# Atishay_EtchASketch.net
KiCad netlist of a schematic drawn in EAGLE
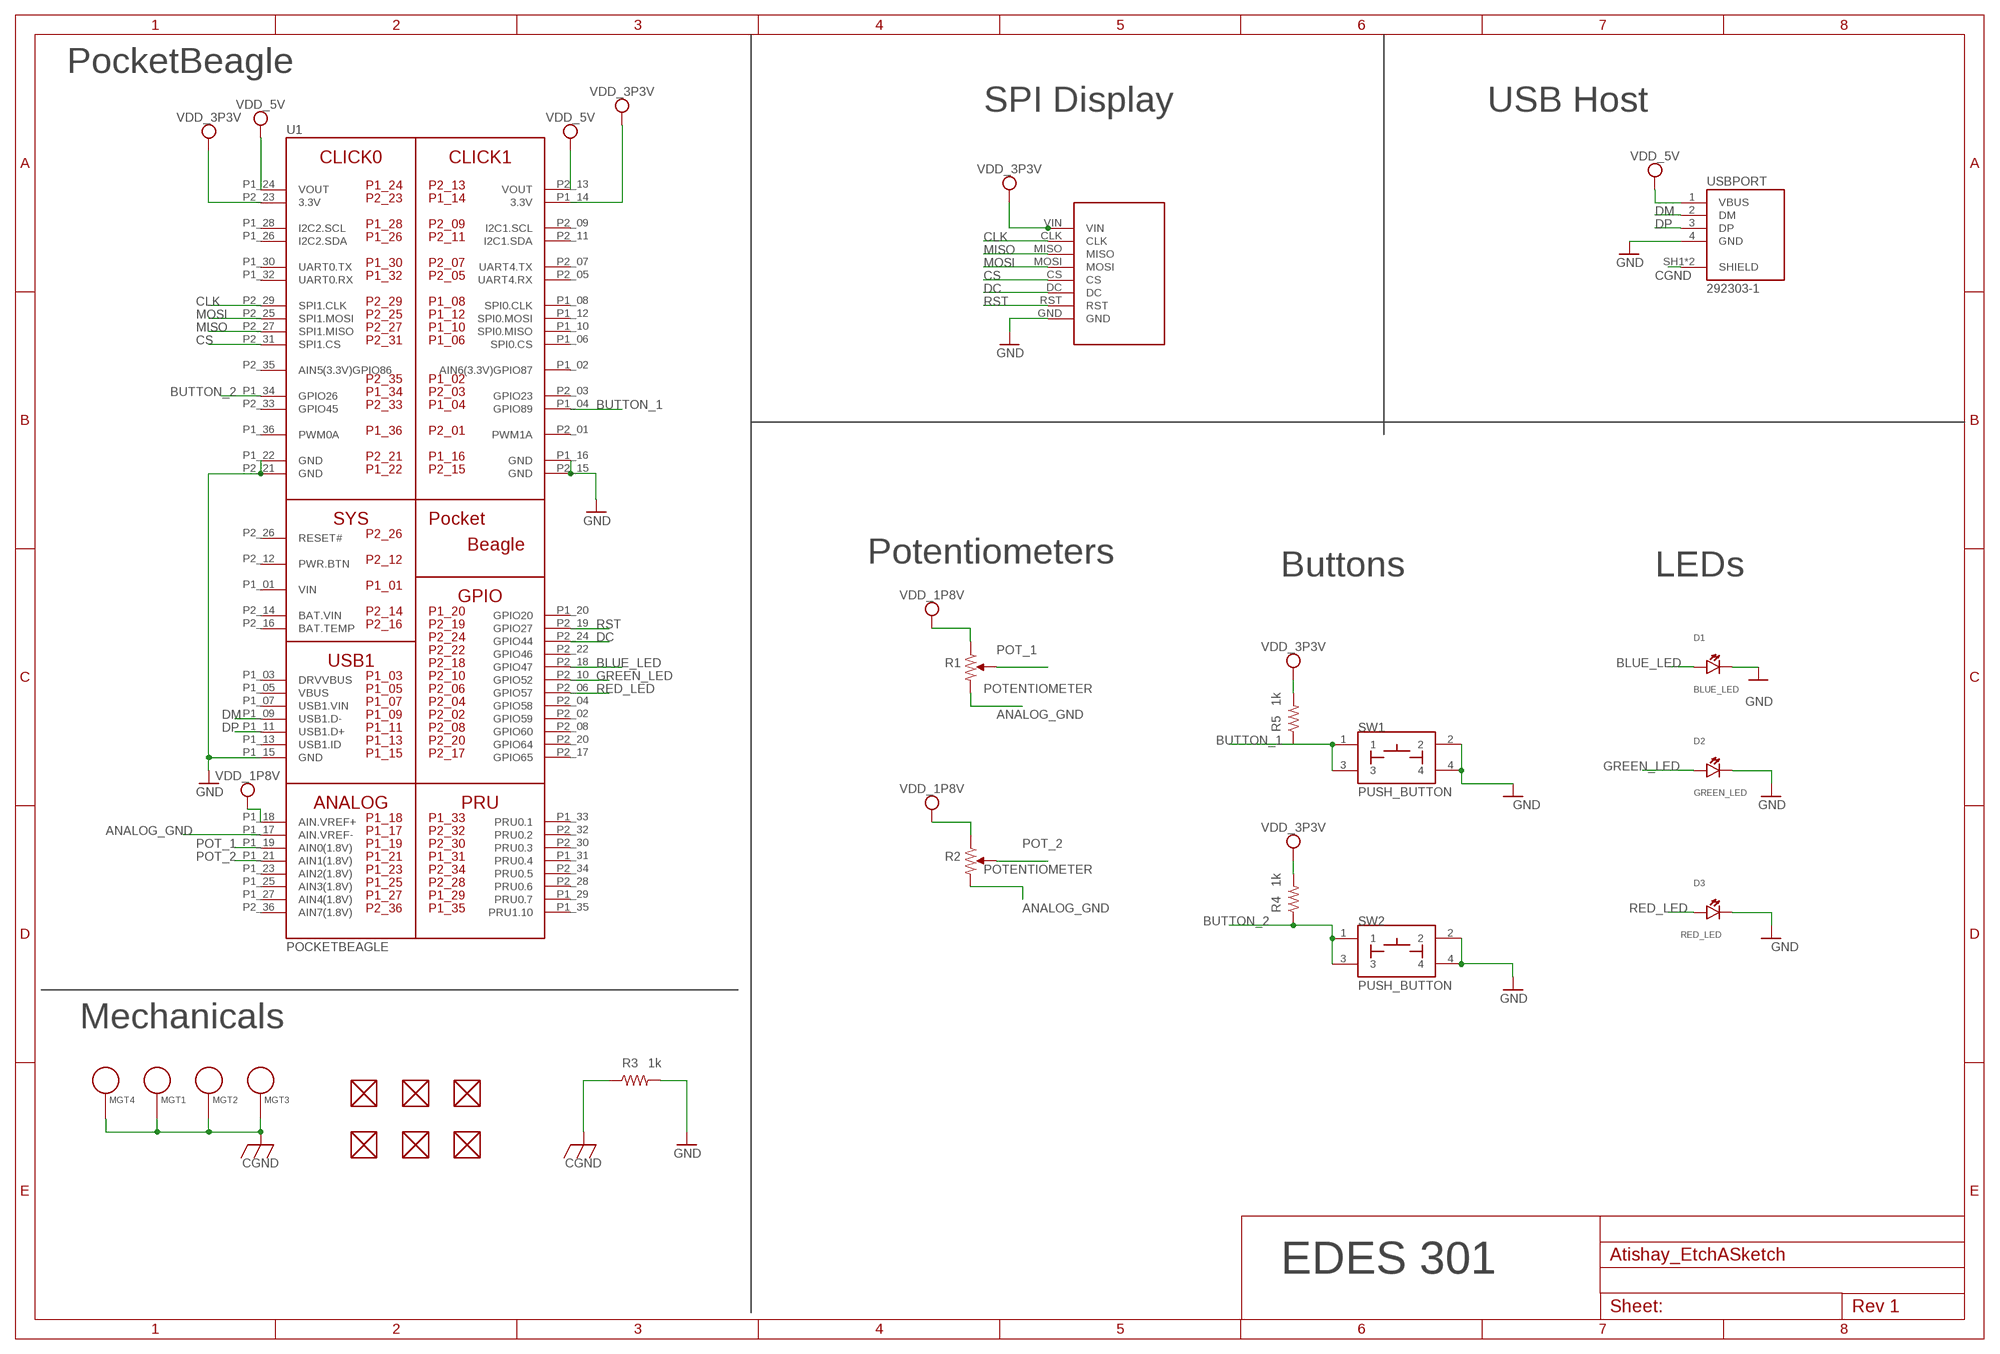
[diagram p0: schematic, sheet 1]

(export (version "E")
  (design (tool "Eeschema 10.0.6"))
  (components
    (comp (ref "D1")
      (value "BLUE_LED")
      (footprint "eagle-import:EIA-STD")
      (libsource (lib "eagle-import") (part "LED"))
    )
    (comp (ref "D2")
      (value "GREEN_LED")
      (footprint "eagle-import:EIA-STD")
      (libsource (lib "eagle-import") (part "LED"))
    )
    (comp (ref "D3")
      (value "RED_LED")
      (footprint "eagle-import:EIA-STD")
      (libsource (lib "eagle-import") (part "LED"))
    )
    (comp (ref "FUD1")
      (value "FIDUCIAL")
      (footprint "eagle-import:FIDUCIAL_40MIL")
      (libsource (lib "eagle-import") (part "FIDUCIAL"))
    )
    (comp (ref "FUD2")
      (value "FIDUCIAL")
      (footprint "eagle-import:FIDUCIAL_40MIL")
      (libsource (lib "eagle-import") (part "FIDUCIAL"))
    )
    (comp (ref "FUD3")
      (value "FIDUCIAL")
      (footprint "eagle-import:FIDUCIAL_40MIL")
      (libsource (lib "eagle-import") (part "FIDUCIAL"))
    )
    (comp (ref "FUD4")
      (value "FIDUCIAL")
      (footprint "eagle-import:FIDUCIAL_40MIL")
      (libsource (lib "eagle-import") (part "FIDUCIAL"))
    )
    (comp (ref "FUD5")
      (value "FIDUCIAL")
      (footprint "eagle-import:FIDUCIAL_40MIL")
      (libsource (lib "eagle-import") (part "FIDUCIAL"))
    )
    (comp (ref "FUD6")
      (value "FIDUCIAL")
      (footprint "eagle-import:FIDUCIAL_40MIL")
      (libsource (lib "eagle-import") (part "FIDUCIAL"))
    )
    (comp (ref "MGT1")
      (value "MOUNTING_HOLE")
      (footprint "eagle-import:MOUNTING_HOLE")
      (libsource (lib "eagle-import") (part "MOUNTING_HOLE"))
    )
    (comp (ref "MGT2")
      (value "MOUNTING_HOLE")
      (footprint "eagle-import:MOUNTING_HOLE")
      (libsource (lib "eagle-import") (part "MOUNTING_HOLE"))
    )
    (comp (ref "MGT3")
      (value "MOUNTING_HOLE")
      (footprint "eagle-import:MOUNTING_HOLE")
      (libsource (lib "eagle-import") (part "MOUNTING_HOLE"))
    )
    (comp (ref "MGT4")
      (value "MOUNTING_HOLE")
      (footprint "eagle-import:MOUNTING_HOLE")
      (libsource (lib "eagle-import") (part "MOUNTING_HOLE"))
    )
    (comp (ref "R1")
      (value "POTENTIOMETER")
      (footprint "eagle-import:POT-PO90S")
      (libsource (lib "eagle-import") (part "POTENTIOMETER"))
    )
    (comp (ref "R2")
      (value "POTENTIOMETER")
      (footprint "eagle-import:POT-PO90S")
      (libsource (lib "eagle-import") (part "POTENTIOMETER"))
    )
    (comp (ref "R3")
      (value "1k")
      (footprint "eagle-import:R0603")
      (libsource (lib "eagle-import") (part "R_R0603"))
    )
    (comp (ref "R4")
      (value "1k")
      (footprint "eagle-import:R0603")
      (libsource (lib "eagle-import") (part "R_R0603"))
    )
    (comp (ref "R5")
      (value "1k")
      (footprint "eagle-import:R0603")
      (libsource (lib "eagle-import") (part "R_R0603"))
    )
    (comp (ref "SPIDISPLAY")
      (value "SCREEN")
      (footprint "eagle-import:SCREEN")
      (libsource (lib "eagle-import") (part "SCREEN"))
    )
    (comp (ref "SW1")
      (value "PUSH_BUTTON")
      (footprint "eagle-import:BUTTON_12.5MM")
      (libsource (lib "eagle-import") (part "PUSH_BUTTON"))
    )
    (comp (ref "SW2")
      (value "PUSH_BUTTON")
      (footprint "eagle-import:BUTTON_12.5MM")
      (libsource (lib "eagle-import") (part "PUSH_BUTTON"))
    )
    (comp (ref "U1")
      (value "POCKETBEAGLE")
      (footprint "eagle-import:POCKETBEAGLE")
      (libsource (lib "eagle-import") (part "POCKETBEAGLE"))
    )
    (comp (ref "USBPORT")
      (value "292303-1")
      (footprint "eagle-import:TE_292303-1")
      (fields (field (name "MF") "TE Connectivity"))
      (libsource (lib "eagle-import") (part "292303-1"))
    )
  )
  (nets
    (net (code "1") (name "/ANALOG_GND") (class "Default")
      (node (ref "R1") (pin "CW") (pinfunction "CW_CW") (pintype "passive"))
      (node (ref "R2") (pin "CW") (pinfunction "CW_CW") (pintype "passive"))
      (node (ref "U1") (pin "P1_17") (pinfunction "AIN.VREF-_P1_17") (pintype "input"))
    )
    (net (code "2") (name "/BAT.VIN") (class "Default")
      (node (ref "U1") (pin "P2_14") (pinfunction "BAT.VIN_P2_14") (pintype "power_in"))
    )
    (net (code "3") (name "/BLUE_LED") (class "Default")
      (node (ref "D1") (pin "ANODE") (pinfunction "ANODE_ANODE") (pintype "bidirectional"))
      (node (ref "U1") (pin "P2_18") (pinfunction "GPIO47_P2_18") (pintype "bidirectional"))
    )
    (net (code "4") (name "/BUTTON_1") (class "Default")
      (node (ref "R5") (pin "1") (pinfunction "1_1") (pintype "passive"))
      (node (ref "SW1") (pin "1") (pinfunction "1_1") (pintype "bidirectional"))
      (node (ref "SW1") (pin "3") (pinfunction "3_3") (pintype "bidirectional"))
      (node (ref "U1") (pin "P1_04") (pinfunction "GPIO89_P1_04") (pintype "bidirectional"))
    )
    (net (code "5") (name "/BUTTON_2") (class "Default")
      (node (ref "R4") (pin "1") (pinfunction "1_1") (pintype "passive"))
      (node (ref "SW2") (pin "1") (pinfunction "1_1") (pintype "bidirectional"))
      (node (ref "SW2") (pin "3") (pinfunction "3_3") (pintype "bidirectional"))
      (node (ref "U1") (pin "P1_34") (pinfunction "GPIO26_P1_34") (pintype "bidirectional"))
    )
    (net (code "6") (name "/CLK") (class "Default")
      (node (ref "SPIDISPLAY") (pin "CLK") (pinfunction "CLK_CLK") (pintype "bidirectional"))
      (node (ref "U1") (pin "P2_29") (pinfunction "SPI1.CLK_P2_29") (pintype "bidirectional"))
    )
    (net (code "7") (name "/CS") (class "Default")
      (node (ref "SPIDISPLAY") (pin "CS") (pinfunction "CS_CS") (pintype "bidirectional"))
      (node (ref "U1") (pin "P2_31") (pinfunction "SPI1.CS_P2_31") (pintype "bidirectional"))
    )
    (net (code "8") (name "/DC") (class "Default")
      (node (ref "SPIDISPLAY") (pin "DC") (pinfunction "DC_DC") (pintype "bidirectional"))
      (node (ref "U1") (pin "P2_24") (pinfunction "GPIO44_P2_24") (pintype "bidirectional"))
    )
    (net (code "9") (name "/DM") (class "Default")
      (node (ref "U1") (pin "P1_09") (pinfunction "USB1.D-_P1_09") (pintype "bidirectional"))
      (node (ref "USBPORT") (pin "2") (pinfunction "DM_2") (pintype "passive"))
    )
    (net (code "10") (name "/DP") (class "Default")
      (node (ref "U1") (pin "P1_11") (pinfunction "USB1.D+_P1_11") (pintype "bidirectional"))
      (node (ref "USBPORT") (pin "3") (pinfunction "DP_3") (pintype "passive"))
    )
    (net (code "11") (name "/GREEN_LED") (class "Default")
      (node (ref "D2") (pin "ANODE") (pinfunction "ANODE_ANODE") (pintype "bidirectional"))
      (node (ref "U1") (pin "P2_10") (pinfunction "GPIO52_P2_10") (pintype "bidirectional"))
    )
    (net (code "12") (name "/MISO") (class "Default")
      (node (ref "SPIDISPLAY") (pin "MISO") (pinfunction "MISO_MISO") (pintype "bidirectional"))
      (node (ref "U1") (pin "P2_27") (pinfunction "SPI1.MISO_P2_27") (pintype "bidirectional"))
    )
    (net (code "13") (name "/MOSI") (class "Default")
      (node (ref "SPIDISPLAY") (pin "MOSI") (pinfunction "MOSI_MOSI") (pintype "bidirectional"))
      (node (ref "U1") (pin "P2_25") (pinfunction "SPI1.MOSI_P2_25") (pintype "bidirectional"))
    )
    (net (code "14") (name "/POT_1") (class "Default")
      (node (ref "R1") (pin "S") (pinfunction "S_S") (pintype "bidirectional"))
      (node (ref "U1") (pin "P1_19") (pinfunction "AIN0(1.8V)_P1_19") (pintype "input"))
    )
    (net (code "15") (name "/POT_2") (class "Default")
      (node (ref "R2") (pin "S") (pinfunction "S_S") (pintype "bidirectional"))
      (node (ref "U1") (pin "P1_21") (pinfunction "AIN1(1.8V)_P1_21") (pintype "input"))
    )
    (net (code "16") (name "/RED_LED") (class "Default")
      (node (ref "D3") (pin "ANODE") (pinfunction "ANODE_ANODE") (pintype "bidirectional"))
      (node (ref "U1") (pin "P2_06") (pinfunction "GPIO57_P2_06") (pintype "bidirectional"))
    )
    (net (code "17") (name "/RST") (class "Default")
      (node (ref "SPIDISPLAY") (pin "RST") (pinfunction "RST_RST") (pintype "bidirectional"))
      (node (ref "U1") (pin "P2_19") (pinfunction "GPIO27_P2_19") (pintype "bidirectional"))
    )
    (net (code "18") (name "/VIN") (class "Default")
      (node (ref "U1") (pin "P1_01") (pinfunction "VIN_P1_01") (pintype "power_in"))
    )
    (net (code "19") (name "CGND") (class "Default")
      (node (ref "MGT1") (pin "P$1") (pinfunction "P$1_P$1") (pintype "bidirectional"))
      (node (ref "MGT2") (pin "P$1") (pinfunction "P$1_P$1") (pintype "bidirectional"))
      (node (ref "MGT3") (pin "P$1") (pinfunction "P$1_P$1") (pintype "bidirectional"))
      (node (ref "MGT4") (pin "P$1") (pinfunction "P$1_P$1") (pintype "bidirectional"))
      (node (ref "R3") (pin "1") (pinfunction "1_1") (pintype "passive"))
      (node (ref "USBPORT") (pin "SH1") (pinfunction "SHIELD_SH1") (pintype "passive"))
      (node (ref "USBPORT") (pin "SH2") (pinfunction "SHIELD_SH2") (pintype "passive"))
    )
    (net (code "20") (name "GND") (class "Default")
      (node (ref "D1") (pin "CATHODE") (pinfunction "CATHODE_CATHODE") (pintype "bidirectional"))
      (node (ref "D2") (pin "CATHODE") (pinfunction "CATHODE_CATHODE") (pintype "bidirectional"))
      (node (ref "D3") (pin "CATHODE") (pinfunction "CATHODE_CATHODE") (pintype "bidirectional"))
      (node (ref "R3") (pin "2") (pinfunction "2_2") (pintype "passive"))
      (node (ref "SPIDISPLAY") (pin "GND") (pinfunction "GND_GND") (pintype "bidirectional"))
      (node (ref "SW1") (pin "2") (pinfunction "2_2") (pintype "bidirectional"))
      (node (ref "SW1") (pin "4") (pinfunction "4_4") (pintype "bidirectional"))
      (node (ref "SW2") (pin "2") (pinfunction "2_2") (pintype "bidirectional"))
      (node (ref "SW2") (pin "4") (pinfunction "4_4") (pintype "bidirectional"))
      (node (ref "U1") (pin "P1_15") (pinfunction "GND_P1_15") (pintype "bidirectional"))
      (node (ref "U1") (pin "P1_16") (pinfunction "GND_P1_16") (pintype "power_in"))
      (node (ref "U1") (pin "P1_22") (pinfunction "GND_P1_22") (pintype "power_in"))
      (node (ref "U1") (pin "P2_15") (pinfunction "GND_P2_15") (pintype "power_in"))
      (node (ref "U1") (pin "P2_21") (pinfunction "GND_P2_21") (pintype "power_in"))
      (node (ref "USBPORT") (pin "4") (pinfunction "GND_4") (pintype "passive"))
    )
    (net (code "21") (name "VDD_1P8V") (class "Default")
      (node (ref "R1") (pin "CCW") (pinfunction "CCW_CCW") (pintype "passive"))
      (node (ref "R2") (pin "CCW") (pinfunction "CCW_CCW") (pintype "passive"))
      (node (ref "U1") (pin "P1_18") (pinfunction "AIN.VREF+_P1_18") (pintype "input"))
    )
    (net (code "22") (name "VDD_3P3V") (class "Default")
      (node (ref "R4") (pin "2") (pinfunction "2_2") (pintype "passive"))
      (node (ref "R5") (pin "2") (pinfunction "2_2") (pintype "passive"))
      (node (ref "SPIDISPLAY") (pin "VIN") (pinfunction "VIN_VIN") (pintype "bidirectional"))
      (node (ref "U1") (pin "P1_14") (pinfunction "3.3V_P1_14") (pintype "power_in"))
      (node (ref "U1") (pin "P2_23") (pinfunction "3.3V_P2_23") (pintype "power_in"))
    )
    (net (code "23") (name "VDD_5V") (class "Default")
      (node (ref "U1") (pin "P1_24") (pinfunction "VOUT_P1_24") (pintype "power_in"))
      (node (ref "U1") (pin "P2_13") (pinfunction "VOUT_P2_13") (pintype "power_in"))
      (node (ref "USBPORT") (pin "1") (pinfunction "VBUS_1") (pintype "passive"))
    )
    (net (code "24") (name "unconnected-(FUD1-PadP$1)") (class "Default")
      (node (ref "FUD1") (pin "P$1") (pinfunction "P$1_P$1") (pintype "no_connect"))
    )
    (net (code "25") (name "unconnected-(FUD2-PadP$1)") (class "Default")
      (node (ref "FUD2") (pin "P$1") (pinfunction "P$1_P$1") (pintype "no_connect"))
    )
    (net (code "26") (name "unconnected-(FUD3-PadP$1)") (class "Default")
      (node (ref "FUD3") (pin "P$1") (pinfunction "P$1_P$1") (pintype "no_connect"))
    )
    (net (code "27") (name "unconnected-(FUD4-PadP$1)") (class "Default")
      (node (ref "FUD4") (pin "P$1") (pinfunction "P$1_P$1") (pintype "no_connect"))
    )
    (net (code "28") (name "unconnected-(FUD5-PadP$1)") (class "Default")
      (node (ref "FUD5") (pin "P$1") (pinfunction "P$1_P$1") (pintype "no_connect"))
    )
    (net (code "29") (name "unconnected-(FUD6-PadP$1)") (class "Default")
      (node (ref "FUD6") (pin "P$1") (pinfunction "P$1_P$1") (pintype "no_connect"))
    )
    (net (code "30") (name "unconnected-(U1-AIN2(1.8V)-PadP1_23)") (class "Default")
      (node (ref "U1") (pin "P1_23") (pinfunction "AIN2(1.8V)_P1_23") (pintype "input"))
    )
    (net (code "31") (name "unconnected-(U1-AIN3(1.8V)-PadP1_25)") (class "Default")
      (node (ref "U1") (pin "P1_25") (pinfunction "AIN3(1.8V)_P1_25") (pintype "input"))
    )
    (net (code "32") (name "unconnected-(U1-AIN4(1.8V)-PadP1_27)") (class "Default")
      (node (ref "U1") (pin "P1_27") (pinfunction "AIN4(1.8V)_P1_27") (pintype "input"))
    )
    (net (code "33") (name "unconnected-(U1-AIN5(3.3V)GPIO86-PadP2_35)") (class "Default")
      (node (ref "U1") (pin "P2_35") (pinfunction "AIN5(3.3V)GPIO86_P2_35") (pintype "bidirectional"))
    )
    (net (code "34") (name "unconnected-(U1-AIN6(3.3V)GPIO87-PadP1_02)") (class "Default")
      (node (ref "U1") (pin "P1_02") (pinfunction "AIN6(3.3V)GPIO87_P1_02") (pintype "bidirectional"))
    )
    (net (code "35") (name "unconnected-(U1-AIN7(1.8V)-PadP2_36)") (class "Default")
      (node (ref "U1") (pin "P2_36") (pinfunction "AIN7(1.8V)_P2_36") (pintype "input"))
    )
    (net (code "36") (name "unconnected-(U1-BAT.TEMP-PadP2_16)") (class "Default")
      (node (ref "U1") (pin "P2_16") (pinfunction "BAT.TEMP_P2_16") (pintype "input"))
    )
    (net (code "37") (name "unconnected-(U1-DRVVBUS-PadP1_03)") (class "Default")
      (node (ref "U1") (pin "P1_03") (pinfunction "DRVVBUS_P1_03") (pintype "bidirectional"))
    )
    (net (code "38") (name "unconnected-(U1-GPIO20-PadP1_20)") (class "Default")
      (node (ref "U1") (pin "P1_20") (pinfunction "GPIO20_P1_20") (pintype "bidirectional"))
    )
    (net (code "39") (name "unconnected-(U1-GPIO23-PadP2_03)") (class "Default")
      (node (ref "U1") (pin "P2_03") (pinfunction "GPIO23_P2_03") (pintype "bidirectional"))
    )
    (net (code "40") (name "unconnected-(U1-GPIO45-PadP2_33)") (class "Default")
      (node (ref "U1") (pin "P2_33") (pinfunction "GPIO45_P2_33") (pintype "bidirectional"))
    )
    (net (code "41") (name "unconnected-(U1-GPIO46-PadP2_22)") (class "Default")
      (node (ref "U1") (pin "P2_22") (pinfunction "GPIO46_P2_22") (pintype "bidirectional"))
    )
    (net (code "42") (name "unconnected-(U1-GPIO58-PadP2_04)") (class "Default")
      (node (ref "U1") (pin "P2_04") (pinfunction "GPIO58_P2_04") (pintype "bidirectional"))
    )
    (net (code "43") (name "unconnected-(U1-GPIO59-PadP2_02)") (class "Default")
      (node (ref "U1") (pin "P2_02") (pinfunction "GPIO59_P2_02") (pintype "bidirectional"))
    )
    (net (code "44") (name "unconnected-(U1-GPIO60-PadP2_08)") (class "Default")
      (node (ref "U1") (pin "P2_08") (pinfunction "GPIO60_P2_08") (pintype "bidirectional"))
    )
    (net (code "45") (name "unconnected-(U1-GPIO64-PadP2_20)") (class "Default")
      (node (ref "U1") (pin "P2_20") (pinfunction "GPIO64_P2_20") (pintype "bidirectional"))
    )
    (net (code "46") (name "unconnected-(U1-GPIO65-PadP2_17)") (class "Default")
      (node (ref "U1") (pin "P2_17") (pinfunction "GPIO65_P2_17") (pintype "bidirectional"))
    )
    (net (code "47") (name "unconnected-(U1-I2C1.SCL-PadP2_09)") (class "Default")
      (node (ref "U1") (pin "P2_09") (pinfunction "I2C1.SCL_P2_09") (pintype "bidirectional"))
    )
    (net (code "48") (name "unconnected-(U1-I2C1.SDA-PadP2_11)") (class "Default")
      (node (ref "U1") (pin "P2_11") (pinfunction "I2C1.SDA_P2_11") (pintype "bidirectional"))
    )
    (net (code "49") (name "unconnected-(U1-I2C2.SCL-PadP1_28)") (class "Default")
      (node (ref "U1") (pin "P1_28") (pinfunction "I2C2.SCL_P1_28") (pintype "bidirectional"))
    )
    (net (code "50") (name "unconnected-(U1-I2C2.SDA-PadP1_26)") (class "Default")
      (node (ref "U1") (pin "P1_26") (pinfunction "I2C2.SDA_P1_26") (pintype "bidirectional"))
    )
    (net (code "51") (name "unconnected-(U1-PRU0.1-PadP1_33)") (class "Default")
      (node (ref "U1") (pin "P1_33") (pinfunction "PRU0.1_P1_33") (pintype "bidirectional"))
    )
    (net (code "52") (name "unconnected-(U1-PRU0.2-PadP2_32)") (class "Default")
      (node (ref "U1") (pin "P2_32") (pinfunction "PRU0.2_P2_32") (pintype "bidirectional"))
    )
    (net (code "53") (name "unconnected-(U1-PRU0.3-PadP2_30)") (class "Default")
      (node (ref "U1") (pin "P2_30") (pinfunction "PRU0.3_P2_30") (pintype "bidirectional"))
    )
    (net (code "54") (name "unconnected-(U1-PRU0.4-PadP1_31)") (class "Default")
      (node (ref "U1") (pin "P1_31") (pinfunction "PRU0.4_P1_31") (pintype "bidirectional"))
    )
    (net (code "55") (name "unconnected-(U1-PRU0.5-PadP2_34)") (class "Default")
      (node (ref "U1") (pin "P2_34") (pinfunction "PRU0.5_P2_34") (pintype "bidirectional"))
    )
    (net (code "56") (name "unconnected-(U1-PRU0.6-PadP2_28)") (class "Default")
      (node (ref "U1") (pin "P2_28") (pinfunction "PRU0.6_P2_28") (pintype "bidirectional"))
    )
    (net (code "57") (name "unconnected-(U1-PRU0.7-PadP1_29)") (class "Default")
      (node (ref "U1") (pin "P1_29") (pinfunction "PRU0.7_P1_29") (pintype "bidirectional"))
    )
    (net (code "58") (name "unconnected-(U1-PRU1.10-PadP1_35)") (class "Default")
      (node (ref "U1") (pin "P1_35") (pinfunction "PRU1.10_P1_35") (pintype "bidirectional"))
    )
    (net (code "59") (name "unconnected-(U1-PWM0A-PadP1_36)") (class "Default")
      (node (ref "U1") (pin "P1_36") (pinfunction "PWM0A_P1_36") (pintype "bidirectional"))
    )
    (net (code "60") (name "unconnected-(U1-PWM1A-PadP2_01)") (class "Default")
      (node (ref "U1") (pin "P2_01") (pinfunction "PWM1A_P2_01") (pintype "bidirectional"))
    )
    (net (code "61") (name "unconnected-(U1-PWR.BTN-PadP2_12)") (class "Default")
      (node (ref "U1") (pin "P2_12") (pinfunction "PWR.BTN_P2_12") (pintype "input"))
    )
    (net (code "62") (name "unconnected-(U1-RESET#-PadP2_26)") (class "Default")
      (node (ref "U1") (pin "P2_26") (pinfunction "RESET#_P2_26") (pintype "input"))
    )
    (net (code "63") (name "unconnected-(U1-SPI0.CLK-PadP1_08)") (class "Default")
      (node (ref "U1") (pin "P1_08") (pinfunction "SPI0.CLK_P1_08") (pintype "bidirectional"))
    )
    (net (code "64") (name "unconnected-(U1-SPI0.CS-PadP1_06)") (class "Default")
      (node (ref "U1") (pin "P1_06") (pinfunction "SPI0.CS_P1_06") (pintype "bidirectional"))
    )
    (net (code "65") (name "unconnected-(U1-SPI0.MISO-PadP1_10)") (class "Default")
      (node (ref "U1") (pin "P1_10") (pinfunction "SPI0.MISO_P1_10") (pintype "bidirectional"))
    )
    (net (code "66") (name "unconnected-(U1-SPI0.MOSI-PadP1_12)") (class "Default")
      (node (ref "U1") (pin "P1_12") (pinfunction "SPI0.MOSI_P1_12") (pintype "bidirectional"))
    )
    (net (code "67") (name "unconnected-(U1-UART0.RX-PadP1_32)") (class "Default")
      (node (ref "U1") (pin "P1_32") (pinfunction "UART0.RX_P1_32") (pintype "bidirectional"))
    )
    (net (code "68") (name "unconnected-(U1-UART0.TX-PadP1_30)") (class "Default")
      (node (ref "U1") (pin "P1_30") (pinfunction "UART0.TX_P1_30") (pintype "bidirectional"))
    )
    (net (code "69") (name "unconnected-(U1-UART4.RX-PadP2_05)") (class "Default")
      (node (ref "U1") (pin "P2_05") (pinfunction "UART4.RX_P2_05") (pintype "bidirectional"))
    )
    (net (code "70") (name "unconnected-(U1-UART4.TX-PadP2_07)") (class "Default")
      (node (ref "U1") (pin "P2_07") (pinfunction "UART4.TX_P2_07") (pintype "bidirectional"))
    )
    (net (code "71") (name "unconnected-(U1-USB1.ID-PadP1_13)") (class "Default")
      (node (ref "U1") (pin "P1_13") (pinfunction "USB1.ID_P1_13") (pintype "bidirectional"))
    )
    (net (code "72") (name "unconnected-(U1-USB1.VIN-PadP1_07)") (class "Default")
      (node (ref "U1") (pin "P1_07") (pinfunction "USB1.VIN_P1_07") (pintype "bidirectional"))
    )
    (net (code "73") (name "unconnected-(U1-VBUS-PadP1_05)") (class "Default")
      (node (ref "U1") (pin "P1_05") (pinfunction "VBUS_P1_05") (pintype "bidirectional"))
    )
  )
)
